# lab4_yz87.net
KiCad netlist of a schematic drawn in EAGLE
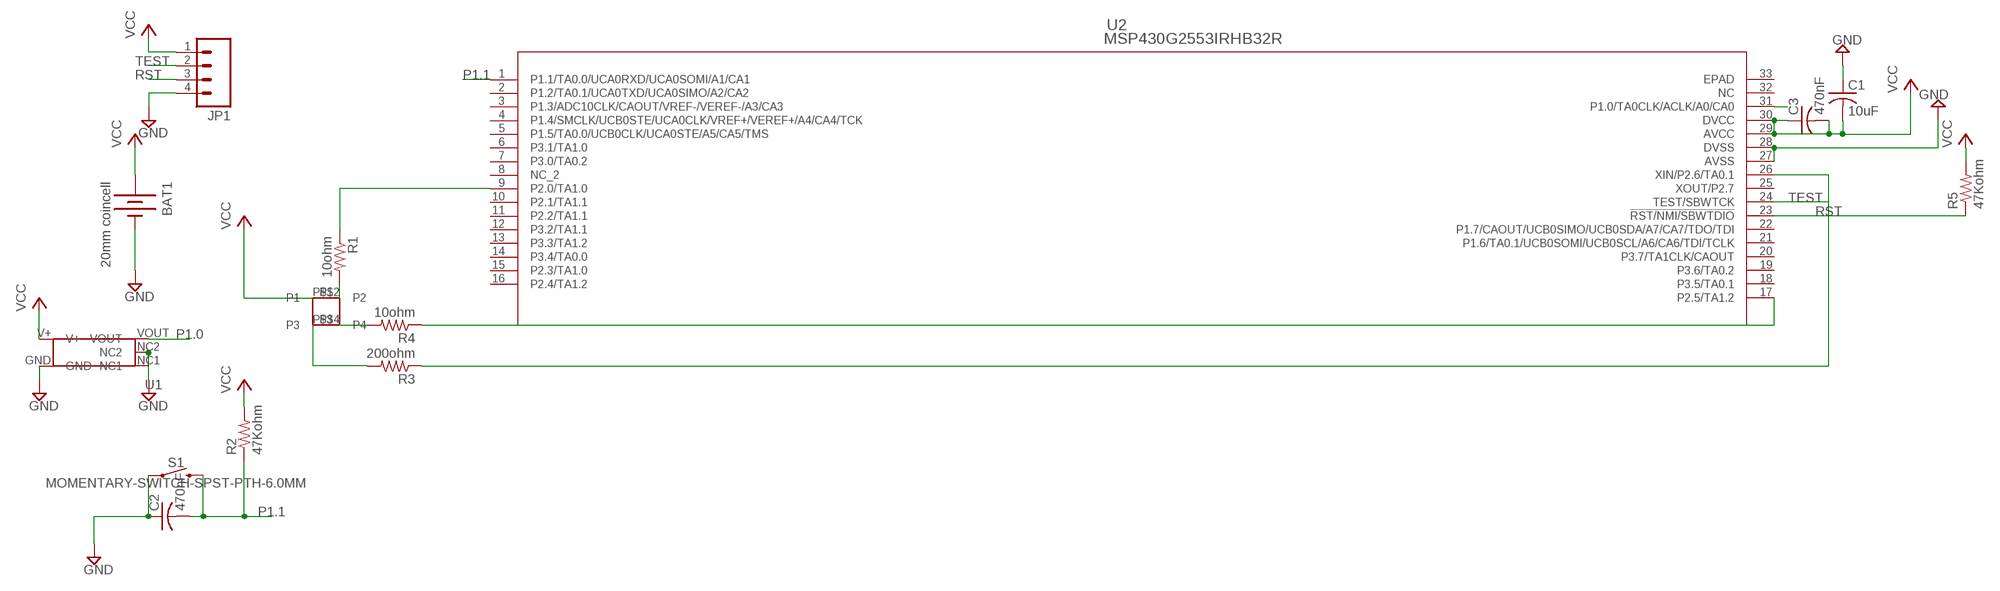
[diagram p0: schematic, sheet 1]

(export (version "E")
  (design (tool "Eeschema 10.0.6"))
  (components
    (comp (ref "BAT1")
      (value "20mm coincell")
      (footprint "eagle-import:BATTCON_20MM_PTH_COMPACT")
      (libsource (lib "eagle-import") (part "BATTERYFOB"))
    )
    (comp (ref "C1")
      (value "10uF")
      (footprint "eagle-import:C1206")
      (libsource (lib "eagle-import") (part "resistor_348_C-USC1206"))
    )
    (comp (ref "C2")
      (value "470nF")
      (footprint "eagle-import:C1206")
      (libsource (lib "eagle-import") (part "C-USC1206"))
    )
    (comp (ref "C3")
      (value "470nF")
      (footprint "eagle-import:C1206")
      (libsource (lib "eagle-import") (part "C-USC1206"))
    )
    (comp (ref "JP1")
      (value "M04LOCK")
      (footprint "eagle-import:1X04_LOCK")
      (libsource (lib "eagle-import") (part "M04LOCK"))
    )
    (comp (ref "R1")
      (value "10ohm")
      (footprint "eagle-import:R1206")
      (libsource (lib "eagle-import") (part "R-US_R1206"))
    )
    (comp (ref "R2")
      (value "47Kohm")
      (footprint "eagle-import:R1206")
      (libsource (lib "eagle-import") (part "R-US_R1206"))
    )
    (comp (ref "R3")
      (value "200ohm")
      (footprint "eagle-import:R1206")
      (libsource (lib "eagle-import") (part "R-US_R1206"))
    )
    (comp (ref "R4")
      (value "10ohm")
      (footprint "eagle-import:R1206")
      (libsource (lib "eagle-import") (part "R-US_R1206"))
    )
    (comp (ref "R5")
      (value "47Kohm")
      (footprint "eagle-import:R1206")
      (libsource (lib "eagle-import") (part "R-US_R1206"))
    )
    (comp (ref "S1")
      (value "MOMENTARY-SWITCH-SPST-PTH-6.0MM")
      (footprint "eagle-import:TACTILE_SWITCH_PTH_6.0MM")
      (libsource (lib "eagle-import") (part "MOMENTARY-SWITCH-SPST-PTH-6.0MM"))
    )
    (comp (ref "U$2")
      (value "RGB_LED")
      (footprint "eagle-import:1210RGB")
      (libsource (lib "eagle-import") (part "RGB_LED"))
    )
    (comp (ref "U1")
      (value "TEMPERATURE_SENSOR")
      (footprint "eagle-import:SOT_563")
      (libsource (lib "eagle-import") (part "TEMPERATURE_SENSOR"))
    )
    (comp (ref "U2")
      (value "MSP430G2553IRHB32R")
      (footprint "eagle-import:RHB32_3P45X3P45")
      (libsource (lib "eagle-import") (part "MSP430G2553IRHB32R"))
    )
  )
  (nets
    (net (code "1") (name "/P1.0") (class "Default")
      (node (ref "U1") (pin "VOUT") (pinfunction "VOUT_VOUT") (pintype "bidirectional"))
      (node (ref "U2") (pin "31") (pinfunction "P1.0/TA0CLK/ACLK/A0/CA0_31") (pintype "bidirectional"))
    )
    (net (code "2") (name "/P1.1") (class "Default")
      (node (ref "C2") (pin "2") (pinfunction "2_2") (pintype "passive"))
      (node (ref "R2") (pin "1") (pinfunction "1_1") (pintype "passive"))
      (node (ref "S1") (pin "3") (pinfunction "2_3") (pintype "passive"))
      (node (ref "U2") (pin "1") (pinfunction "P1.1/TA0.0/UCA0RXD/UCA0SOMI/A1/CA1_1") (pintype "bidirectional"))
    )
    (net (code "3") (name "/RST") (class "Default")
      (node (ref "JP1") (pin "3") (pinfunction "3_3") (pintype "passive"))
      (node (ref "R5") (pin "1") (pinfunction "1_1") (pintype "passive"))
      (node (ref "U2") (pin "23") (pinfunction "~{RST/NMI/SBWTDIO}_23") (pintype "bidirectional"))
    )
    (net (code "4") (name "/TEST") (class "Default")
      (node (ref "JP1") (pin "2") (pinfunction "2_2") (pintype "passive"))
      (node (ref "U2") (pin "24") (pinfunction "TEST/SBWTCK_24") (pintype "bidirectional"))
    )
    (net (code "5") (name "GND") (class "Default")
      (node (ref "BAT1") (pin "2") (pinfunction "-_2") (pintype "power_in"))
      (node (ref "C1") (pin "1") (pinfunction "1_1") (pintype "passive"))
      (node (ref "C2") (pin "1") (pinfunction "1_1") (pintype "passive"))
      (node (ref "JP1") (pin "4") (pinfunction "4_4") (pintype "passive"))
      (node (ref "S1") (pin "1") (pinfunction "1_1") (pintype "passive"))
      (node (ref "U1") (pin "GND") (pinfunction "GND_GND") (pintype "bidirectional"))
      (node (ref "U1") (pin "NC1") (pinfunction "NC1_NC1") (pintype "bidirectional"))
      (node (ref "U1") (pin "NC2") (pinfunction "NC2_NC2") (pintype "bidirectional"))
      (node (ref "U2") (pin "27") (pinfunction "AVSS_27") (pintype "power_in"))
      (node (ref "U2") (pin "28") (pinfunction "DVSS_28") (pintype "power_in"))
    )
    (net (code "6") (name "Net-(U$2-P2)") (class "Default")
      (node (ref "R1") (pin "2") (pinfunction "2_2") (pintype "passive"))
      (node (ref "U$2") (pin "P$2") (pinfunction "P2_P$2") (pintype "bidirectional"))
    )
    (net (code "7") (name "Net-(U$2-P3)") (class "Default")
      (node (ref "R3") (pin "2") (pinfunction "2_2") (pintype "passive"))
      (node (ref "U$2") (pin "P$3") (pinfunction "P3_P$3") (pintype "bidirectional"))
    )
    (net (code "8") (name "Net-(U$2-P4)") (class "Default")
      (node (ref "R4") (pin "2") (pinfunction "2_2") (pintype "passive"))
      (node (ref "U$2") (pin "P$4") (pinfunction "P4_P$4") (pintype "bidirectional"))
    )
    (net (code "9") (name "Net-(U2-P2.0{slash}TA1.0)") (class "Default")
      (node (ref "R1") (pin "1") (pinfunction "1_1") (pintype "passive"))
      (node (ref "U2") (pin "9") (pinfunction "P2.0/TA1.0_9") (pintype "bidirectional"))
    )
    (net (code "10") (name "Net-(U2-P2.5{slash}TA1.2)") (class "Default")
      (node (ref "R4") (pin "1") (pinfunction "1_1") (pintype "passive"))
      (node (ref "U2") (pin "17") (pinfunction "P2.5/TA1.2_17") (pintype "bidirectional"))
    )
    (net (code "11") (name "Net-(U2-XIN{slash}P2.6{slash}TA0.1)") (class "Default")
      (node (ref "R3") (pin "1") (pinfunction "1_1") (pintype "passive"))
      (node (ref "U2") (pin "26") (pinfunction "XIN/P2.6/TA0.1_26") (pintype "bidirectional"))
    )
    (net (code "12") (name "VCC") (class "Default")
      (node (ref "BAT1") (pin "1") (pinfunction "+_1") (pintype "power_in"))
      (node (ref "BAT1") (pin "3") (pinfunction "+_3") (pintype "power_in"))
      (node (ref "BAT1") (pin "4") (pinfunction "+_4") (pintype "power_in"))
      (node (ref "BAT1") (pin "5") (pinfunction "+_5") (pintype "power_in"))
      (node (ref "C1") (pin "2") (pinfunction "2_2") (pintype "passive"))
      (node (ref "C3") (pin "1") (pinfunction "1_1") (pintype "passive"))
      (node (ref "C3") (pin "2") (pinfunction "2_2") (pintype "passive"))
      (node (ref "JP1") (pin "1") (pinfunction "1_1") (pintype "passive"))
      (node (ref "R2") (pin "2") (pinfunction "2_2") (pintype "passive"))
      (node (ref "R5") (pin "2") (pinfunction "2_2") (pintype "passive"))
      (node (ref "U$2") (pin "P$1") (pinfunction "P1_P$1") (pintype "bidirectional"))
      (node (ref "U1") (pin "V+") (pinfunction "V+_V+") (pintype "bidirectional"))
      (node (ref "U2") (pin "29") (pinfunction "AVCC_29") (pintype "power_in"))
      (node (ref "U2") (pin "30") (pinfunction "DVCC_30") (pintype "power_in"))
    )
    (net (code "13") (name "unconnected-(U2-EPAD-Pad33)") (class "Default")
      (node (ref "U2") (pin "33") (pinfunction "EPAD_33") (pintype "passive"))
    )
    (net (code "14") (name "unconnected-(U2-NC-Pad32)") (class "Default")
      (node (ref "U2") (pin "32") (pinfunction "NC_32") (pintype "passive"))
    )
    (net (code "15") (name "unconnected-(U2-NC_2-Pad8)") (class "Default")
      (node (ref "U2") (pin "8") (pinfunction "NC_2_8") (pintype "passive"))
    )
    (net (code "16") (name "unconnected-(U2-P1.2{slash}TA0.1{slash}UCA0TXD{slash}UCA0SIMO{slash}A2{slash}CA2-Pad2)") (class "Default")
      (node (ref "U2") (pin "2") (pinfunction "P1.2/TA0.1/UCA0TXD/UCA0SIMO/A2/CA2_2") (pintype "bidirectional"))
    )
    (net (code "17") (name "unconnected-(U2-P1.3{slash}ADC10CLK{slash}CAOUT{slash}VREF-{slash}VEREF-{slash}A3{slash}CA3-Pad3)") (class "Default")
      (node (ref "U2") (pin "3") (pinfunction "P1.3/ADC10CLK/CAOUT/VREF-/VEREF-/A3/CA3_3") (pintype "bidirectional"))
    )
    (net (code "18") (name "unconnected-(U2-P1.4{slash}SMCLK{slash}UCB0STE{slash}UCA0CLK{slash}VREF+{slash}VEREF+{slash}A4{slash}CA4{slash}TCK-Pad4)") (class "Default")
      (node (ref "U2") (pin "4") (pinfunction "P1.4/SMCLK/UCB0STE/UCA0CLK/VREF+/VEREF+/A4/CA4/TCK_4") (pintype "bidirectional"))
    )
    (net (code "19") (name "unconnected-(U2-P1.5{slash}TA0.0{slash}UCB0CLK{slash}UCA0STE{slash}A5{slash}CA5{slash}TMS-Pad5)") (class "Default")
      (node (ref "U2") (pin "5") (pinfunction "P1.5/TA0.0/UCB0CLK/UCA0STE/A5/CA5/TMS_5") (pintype "bidirectional"))
    )
    (net (code "20") (name "unconnected-(U2-P1.6{slash}TA0.1{slash}UCB0SOMI{slash}UCB0SCL{slash}A6{slash}CA6{slash}TDI{slash}TCLK-Pad21)") (class "Default")
      (node (ref "U2") (pin "21") (pinfunction "P1.6/TA0.1/UCB0SOMI/UCB0SCL/A6/CA6/TDI/TCLK_21") (pintype "bidirectional"))
    )
    (net (code "21") (name "unconnected-(U2-P1.7{slash}CAOUT{slash}UCB0SIMO{slash}UCB0SDA{slash}A7{slash}CA7{slash}TDO{slash}TDI-Pad22)") (class "Default")
      (node (ref "U2") (pin "22") (pinfunction "P1.7/CAOUT/UCB0SIMO/UCB0SDA/A7/CA7/TDO/TDI_22") (pintype "bidirectional"))
    )
    (net (code "22") (name "unconnected-(U2-P2.1{slash}TA1.1-Pad10)") (class "Default")
      (node (ref "U2") (pin "10") (pinfunction "P2.1/TA1.1_10") (pintype "bidirectional"))
    )
    (net (code "23") (name "unconnected-(U2-P2.2{slash}TA1.1-Pad11)") (class "Default")
      (node (ref "U2") (pin "11") (pinfunction "P2.2/TA1.1_11") (pintype "bidirectional"))
    )
    (net (code "24") (name "unconnected-(U2-P2.3{slash}TA1.0-Pad15)") (class "Default")
      (node (ref "U2") (pin "15") (pinfunction "P2.3/TA1.0_15") (pintype "bidirectional"))
    )
    (net (code "25") (name "unconnected-(U2-P2.4{slash}TA1.2-Pad16)") (class "Default")
      (node (ref "U2") (pin "16") (pinfunction "P2.4/TA1.2_16") (pintype "bidirectional"))
    )
    (net (code "26") (name "unconnected-(U2-P3.0{slash}TA0.2-Pad7)") (class "Default")
      (node (ref "U2") (pin "7") (pinfunction "P3.0/TA0.2_7") (pintype "bidirectional"))
    )
    (net (code "27") (name "unconnected-(U2-P3.1{slash}TA1.0-Pad6)") (class "Default")
      (node (ref "U2") (pin "6") (pinfunction "P3.1/TA1.0_6") (pintype "bidirectional"))
    )
    (net (code "28") (name "unconnected-(U2-P3.2{slash}TA1.1-Pad12)") (class "Default")
      (node (ref "U2") (pin "12") (pinfunction "P3.2/TA1.1_12") (pintype "bidirectional"))
    )
    (net (code "29") (name "unconnected-(U2-P3.3{slash}TA1.2-Pad13)") (class "Default")
      (node (ref "U2") (pin "13") (pinfunction "P3.3/TA1.2_13") (pintype "bidirectional"))
    )
    (net (code "30") (name "unconnected-(U2-P3.4{slash}TA0.0-Pad14)") (class "Default")
      (node (ref "U2") (pin "14") (pinfunction "P3.4/TA0.0_14") (pintype "bidirectional"))
    )
    (net (code "31") (name "unconnected-(U2-P3.5{slash}TA0.1-Pad18)") (class "Default")
      (node (ref "U2") (pin "18") (pinfunction "P3.5/TA0.1_18") (pintype "bidirectional"))
    )
    (net (code "32") (name "unconnected-(U2-P3.6{slash}TA0.2-Pad19)") (class "Default")
      (node (ref "U2") (pin "19") (pinfunction "P3.6/TA0.2_19") (pintype "bidirectional"))
    )
    (net (code "33") (name "unconnected-(U2-P3.7{slash}TA1CLK{slash}CAOUT-Pad20)") (class "Default")
      (node (ref "U2") (pin "20") (pinfunction "P3.7/TA1CLK/CAOUT_20") (pintype "bidirectional"))
    )
    (net (code "34") (name "unconnected-(U2-XOUT{slash}P2.7-Pad25)") (class "Default")
      (node (ref "U2") (pin "25") (pinfunction "XOUT/P2.7_25") (pintype "bidirectional"))
    )
  )
)
